# xmas_tree.net
KiCad netlist of a schematic drawn in EAGLE
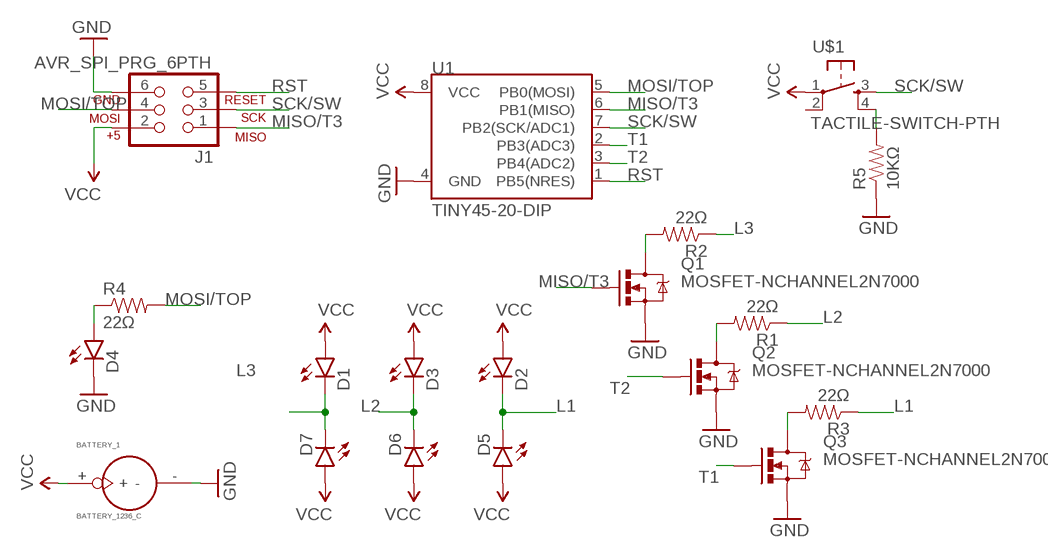
[diagram p0: schematic, sheet 1]

(export (version "E")
  (design (tool "Eeschema 10.0.6"))
  (components
    (comp (ref "BATTERY_1")
      (value "BATTERY_1236_C")
      (footprint "eagle-import:BATTERY_1236_C")
      (libsource (lib "eagle-import") (part "BATTERY_1236_C"))
    )
    (comp (ref "D1")
      (value "LED")
      (footprint "eagle-import:LED5MM-SLIM")
      (libsource (lib "eagle-import") (part "LED"))
    )
    (comp (ref "D2")
      (value "LED")
      (footprint "eagle-import:LED5MM-SLIM")
      (libsource (lib "eagle-import") (part "LED"))
    )
    (comp (ref "D3")
      (value "LED")
      (footprint "eagle-import:LED5MM-SLIM")
      (libsource (lib "eagle-import") (part "LED"))
    )
    (comp (ref "D4")
      (value "LED")
      (footprint "eagle-import:LED5MM-SLIM")
      (libsource (lib "eagle-import") (part "LED"))
    )
    (comp (ref "D5")
      (value "LED")
      (footprint "eagle-import:LED5MM-SLIM")
      (libsource (lib "eagle-import") (part "LED"))
    )
    (comp (ref "D6")
      (value "LED")
      (footprint "eagle-import:LED5MM-SLIM")
      (libsource (lib "eagle-import") (part "LED"))
    )
    (comp (ref "D7")
      (value "LED")
      (footprint "eagle-import:LED5MM-SLIM")
      (libsource (lib "eagle-import") (part "LED"))
    )
    (comp (ref "J1")
      (value "AVR_SPI_PRG_6PTH")
      (footprint "eagle-import:2X3")
      (libsource (lib "eagle-import") (part "AVR_SPI_PRG_6PTH"))
    )
    (comp (ref "Q1")
      (value "MOSFET-NCHANNEL2N7000")
      (footprint "eagle-import:TO-92")
      (libsource (lib "eagle-import") (part "MOSFET-NCHANNEL2N7000"))
    )
    (comp (ref "Q2")
      (value "MOSFET-NCHANNEL2N7000")
      (footprint "eagle-import:TO-92")
      (libsource (lib "eagle-import") (part "MOSFET-NCHANNEL2N7000"))
    )
    (comp (ref "Q3")
      (value "MOSFET-NCHANNEL2N7000")
      (footprint "eagle-import:TO-92")
      (libsource (lib "eagle-import") (part "MOSFET-NCHANNEL2N7000"))
    )
    (comp (ref "R1")
      (value "22Ω")
      (footprint "eagle-import:1206")
      (libsource (lib "eagle-import") (part "RESISTOR1206"))
    )
    (comp (ref "R2")
      (value "22Ω")
      (footprint "eagle-import:1206")
      (libsource (lib "eagle-import") (part "RESISTOR1206"))
    )
    (comp (ref "R3")
      (value "22Ω")
      (footprint "eagle-import:1206")
      (libsource (lib "eagle-import") (part "RESISTOR1206"))
    )
    (comp (ref "R4")
      (value "22Ω")
      (footprint "eagle-import:1206")
      (libsource (lib "eagle-import") (part "RESISTOR1206"))
    )
    (comp (ref "R5")
      (value "10KΩ")
      (footprint "eagle-import:1206")
      (libsource (lib "eagle-import") (part "RESISTOR1206"))
    )
    (comp (ref "U$1")
      (value "TACTILE-SWITCH-PTH")
      (footprint "eagle-import:TAC-SWITCH-PTH")
      (libsource (lib "eagle-import") (part "TACTILE-SWITCH-PTH"))
    )
    (comp (ref "U1")
      (value "TINY45-20-DIP")
      (footprint "eagle-import:DIP08")
      (libsource (lib "eagle-import") (part "ATTINY45TINY45-20-DIP"))
    )
  )
  (nets
    (net (code "1") (name "/L1") (class "Default")
      (node (ref "D2") (pin "K") (pinfunction "C_K") (pintype "passive"))
      (node (ref "D5") (pin "K") (pinfunction "C_K") (pintype "passive"))
      (node (ref "R3") (pin "1") (pinfunction "1_1") (pintype "passive"))
    )
    (net (code "2") (name "/L2") (class "Default")
      (node (ref "D3") (pin "K") (pinfunction "C_K") (pintype "passive"))
      (node (ref "D6") (pin "K") (pinfunction "C_K") (pintype "passive"))
      (node (ref "R1") (pin "1") (pinfunction "1_1") (pintype "passive"))
    )
    (net (code "3") (name "/L3") (class "Default")
      (node (ref "D1") (pin "K") (pinfunction "C_K") (pintype "passive"))
      (node (ref "D7") (pin "K") (pinfunction "C_K") (pintype "passive"))
      (node (ref "R2") (pin "1") (pinfunction "1_1") (pintype "passive"))
    )
    (net (code "4") (name "/MISO{slash}T3") (class "Default")
      (node (ref "J1") (pin "1") (pinfunction "1_1") (pintype "passive"))
      (node (ref "Q1") (pin "2") (pinfunction "G_2") (pintype "passive"))
      (node (ref "U1") (pin "6") (pinfunction "PB1(MISO)_6") (pintype "bidirectional"))
    )
    (net (code "5") (name "/MOSI{slash}TOP") (class "Default")
      (node (ref "J1") (pin "4") (pinfunction "4_4") (pintype "passive"))
      (node (ref "R4") (pin "2") (pinfunction "2_2") (pintype "passive"))
      (node (ref "U1") (pin "5") (pinfunction "PB0(MOSI)_5") (pintype "bidirectional"))
    )
    (net (code "6") (name "/RST") (class "Default")
      (node (ref "J1") (pin "5") (pinfunction "5_5") (pintype "passive"))
      (node (ref "U1") (pin "1") (pinfunction "PB5(NRES)_1") (pintype "bidirectional"))
    )
    (net (code "7") (name "/SCK{slash}SW") (class "Default")
      (node (ref "J1") (pin "3") (pinfunction "3_3") (pintype "passive"))
      (node (ref "U$1") (pin "3") (pinfunction "3_3") (pintype "passive"))
      (node (ref "U1") (pin "7") (pinfunction "PB2(SCK/ADC1)_7") (pintype "bidirectional"))
    )
    (net (code "8") (name "/T1") (class "Default")
      (node (ref "Q3") (pin "2") (pinfunction "G_2") (pintype "passive"))
      (node (ref "U1") (pin "2") (pinfunction "PB3(ADC3)_2") (pintype "bidirectional"))
    )
    (net (code "9") (name "/T2") (class "Default")
      (node (ref "Q2") (pin "2") (pinfunction "G_2") (pintype "passive"))
      (node (ref "U1") (pin "3") (pinfunction "PB4(ADC2)_3") (pintype "bidirectional"))
    )
    (net (code "10") (name "GND") (class "Default")
      (node (ref "BATTERY_1") (pin "-") (pinfunction "-_-") (pintype "bidirectional"))
      (node (ref "D4") (pin "K") (pinfunction "C_K") (pintype "passive"))
      (node (ref "J1") (pin "6") (pinfunction "6_6") (pintype "passive"))
      (node (ref "Q1") (pin "1") (pinfunction "S_1") (pintype "passive"))
      (node (ref "Q2") (pin "1") (pinfunction "S_1") (pintype "passive"))
      (node (ref "Q3") (pin "1") (pinfunction "S_1") (pintype "passive"))
      (node (ref "R5") (pin "1") (pinfunction "1_1") (pintype "passive"))
      (node (ref "U1") (pin "4") (pinfunction "GND_4") (pintype "bidirectional"))
    )
    (net (code "11") (name "Net-(D4-PadA)") (class "Default")
      (node (ref "D4") (pin "A") (pinfunction "A_A") (pintype "passive"))
      (node (ref "R4") (pin "1") (pinfunction "1_1") (pintype "passive"))
    )
    (net (code "12") (name "Net-(Q1-D)") (class "Default")
      (node (ref "Q1") (pin "3") (pinfunction "D_3") (pintype "passive"))
      (node (ref "R2") (pin "2") (pinfunction "2_2") (pintype "passive"))
    )
    (net (code "13") (name "Net-(Q2-D)") (class "Default")
      (node (ref "Q2") (pin "3") (pinfunction "D_3") (pintype "passive"))
      (node (ref "R1") (pin "2") (pinfunction "2_2") (pintype "passive"))
    )
    (net (code "14") (name "Net-(Q3-D)") (class "Default")
      (node (ref "Q3") (pin "3") (pinfunction "D_3") (pintype "passive"))
      (node (ref "R3") (pin "2") (pinfunction "2_2") (pintype "passive"))
    )
    (net (code "15") (name "Net-(R5-Pad2)") (class "Default")
      (node (ref "R5") (pin "2") (pinfunction "2_2") (pintype "passive"))
      (node (ref "U$1") (pin "4") (pinfunction "4_4") (pintype "passive"))
    )
    (net (code "16") (name "VCC") (class "Default")
      (node (ref "BATTERY_1") (pin "+") (pinfunction "+_+") (pintype "bidirectional"))
      (node (ref "D1") (pin "A") (pinfunction "A_A") (pintype "passive"))
      (node (ref "D2") (pin "A") (pinfunction "A_A") (pintype "passive"))
      (node (ref "D3") (pin "A") (pinfunction "A_A") (pintype "passive"))
      (node (ref "D5") (pin "A") (pinfunction "A_A") (pintype "passive"))
      (node (ref "D6") (pin "A") (pinfunction "A_A") (pintype "passive"))
      (node (ref "D7") (pin "A") (pinfunction "A_A") (pintype "passive"))
      (node (ref "J1") (pin "2") (pinfunction "2_2") (pintype "passive"))
      (node (ref "U$1") (pin "1") (pinfunction "1_1") (pintype "passive"))
      (node (ref "U1") (pin "8") (pinfunction "VCC_8") (pintype "bidirectional"))
    )
    (net (code "17") (name "unconnected-(U$1-Pad2)") (class "Default")
      (node (ref "U$1") (pin "2") (pinfunction "2_2") (pintype "passive"))
    )
  )
)
